# Flash_Fashion_Schematic_V2.net
KiCad netlist of a schematic drawn in EAGLE
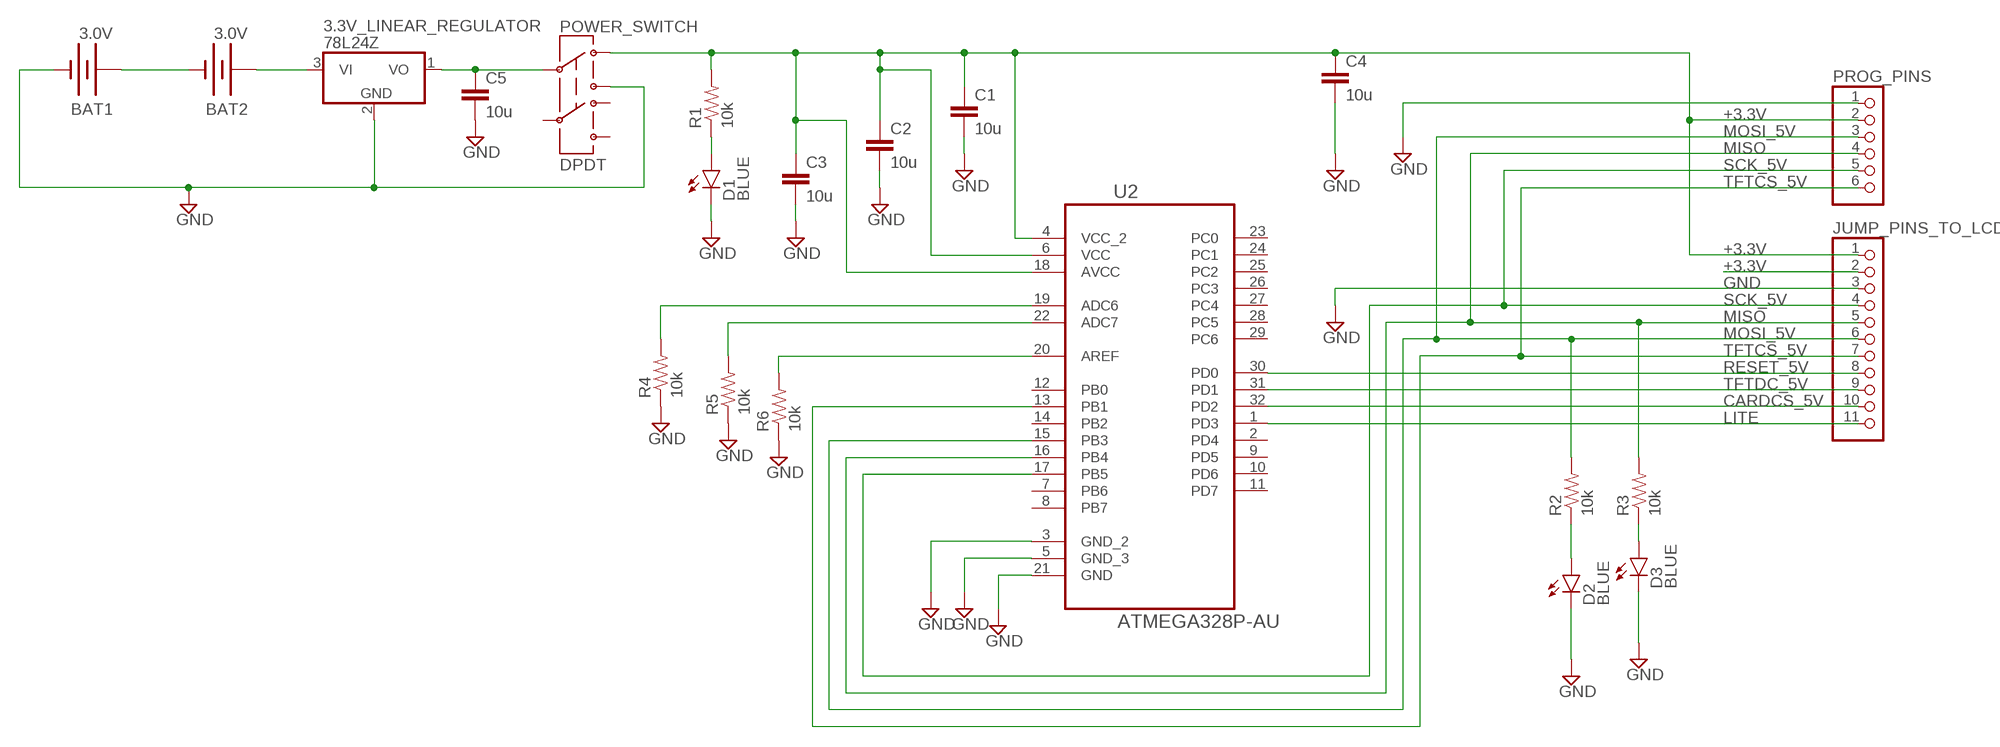
[diagram p0: schematic, sheet 1]

(export (version "E")
  (design (tool "Eeschema 10.0.6"))
  (components
    (comp (ref "3.3V_LINEAR_REGULATOR")
      (value "78L24Z")
      (footprint "eagle-import:TO92")
      (libsource (lib "eagle-import") (part "78ZL24"))
    )
    (comp (ref "BAT1")
      (value "3.0V")
      (footprint "eagle-import:BATTCON_245MM_PTH")
      (libsource (lib "eagle-import") (part "BATTERY245PTH"))
    )
    (comp (ref "BAT2")
      (value "3.0V")
      (footprint "eagle-import:BATTCON_245MM_PTH")
      (libsource (lib "eagle-import") (part "BATTERY245PTH"))
    )
    (comp (ref "C1")
      (value "10u")
      (footprint "eagle-import:1206")
      (libsource (lib "eagle-import") (part "CAP1206"))
    )
    (comp (ref "C2")
      (value "10u")
      (footprint "eagle-import:1206")
      (libsource (lib "eagle-import") (part "CAP1206"))
    )
    (comp (ref "C3")
      (value "10u")
      (footprint "eagle-import:1206")
      (libsource (lib "eagle-import") (part "CAP1206"))
    )
    (comp (ref "C4")
      (value "10u")
      (footprint "eagle-import:1206")
      (libsource (lib "eagle-import") (part "CAP1206"))
    )
    (comp (ref "C5")
      (value "10u")
      (footprint "eagle-import:1206")
      (libsource (lib "eagle-import") (part "CAP1206"))
    )
    (comp (ref "D1")
      (value "BLUE")
      (footprint "eagle-import:LED-1206")
      (libsource (lib "eagle-import") (part "LED-BLUE1206"))
    )
    (comp (ref "D2")
      (value "BLUE")
      (footprint "eagle-import:LED-1206")
      (libsource (lib "eagle-import") (part "LED-BLUE1206"))
    )
    (comp (ref "D3")
      (value "BLUE")
      (footprint "eagle-import:LED-1206")
      (libsource (lib "eagle-import") (part "LED-BLUE1206"))
    )
    (comp (ref "JUMP_PINS_TO_LCD")
      (value "HEADER-1X1176MIL")
      (footprint "eagle-import:1X11_ROUND_76")
      (libsource (lib "eagle-import") (part "HEADER-1X1176MIL"))
    )
    (comp (ref "POWER_SWITCH")
      (value "DPDT")
      (footprint "eagle-import:AYZ0202")
      (libsource (lib "eagle-import") (part "SWITCH-DPDTAYZ0202"))
    )
    (comp (ref "PROG_PINS")
      (value "PINHD-1X6-3.5MM")
      (footprint "eagle-import:1X06-3.5MM")
      (libsource (lib "eagle-import") (part "PINHD-1X6-3.5MM"))
    )
    (comp (ref "R1")
      (value "10k")
      (footprint "eagle-import:1206")
      (libsource (lib "eagle-import") (part "RESISTOR1206"))
    )
    (comp (ref "R2")
      (value "10k")
      (footprint "eagle-import:1206")
      (libsource (lib "eagle-import") (part "RESISTOR1206"))
    )
    (comp (ref "R3")
      (value "10k")
      (footprint "eagle-import:1206")
      (libsource (lib "eagle-import") (part "RESISTOR1206"))
    )
    (comp (ref "R4")
      (value "10k")
      (footprint "eagle-import:1206")
      (libsource (lib "eagle-import") (part "RESISTOR1206"))
    )
    (comp (ref "R5")
      (value "10k")
      (footprint "eagle-import:1206")
      (libsource (lib "eagle-import") (part "RESISTOR1206"))
    )
    (comp (ref "R6")
      (value "10k")
      (footprint "eagle-import:1206")
      (libsource (lib "eagle-import") (part "RESISTOR1206"))
    )
    (comp (ref "U2")
      (value "ATMEGA328P-AU")
      (footprint "eagle-import:QFP80P900X900X120-32N")
      (libsource (lib "eagle-import") (part "ATMEGA328P-AU"))
    )
  )
  (nets
    (net (code "1") (name "/+3.3V") (class "Default")
      (node (ref "C1") (pin "1") (pinfunction "1_1") (pintype "passive"))
      (node (ref "C2") (pin "1") (pinfunction "1_1") (pintype "passive"))
      (node (ref "C3") (pin "1") (pinfunction "1_1") (pintype "passive"))
      (node (ref "C4") (pin "1") (pinfunction "1_1") (pintype "passive"))
      (node (ref "JUMP_PINS_TO_LCD") (pin "1") (pinfunction "1_1") (pintype "passive"))
      (node (ref "POWER_SWITCH") (pin "1") (pinfunction "1_1") (pintype "bidirectional"))
      (node (ref "PROG_PINS") (pin "2") (pinfunction "2_2") (pintype "passive"))
      (node (ref "R1") (pin "2") (pinfunction "2_2") (pintype "passive"))
      (node (ref "U2") (pin "18") (pinfunction "AVCC_18") (pintype "power_in"))
      (node (ref "U2") (pin "4") (pinfunction "VCC_2_4") (pintype "power_in"))
      (node (ref "U2") (pin "6") (pinfunction "VCC_6") (pintype "power_in"))
    )
    (net (code "2") (name "/CARDCS_5V") (class "Default")
      (node (ref "JUMP_PINS_TO_LCD") (pin "10") (pinfunction "10_10") (pintype "passive"))
      (node (ref "U2") (pin "32") (pinfunction "PD2_32") (pintype "bidirectional"))
    )
    (net (code "3") (name "/LITE") (class "Default")
      (node (ref "JUMP_PINS_TO_LCD") (pin "11") (pinfunction "11_11") (pintype "passive"))
      (node (ref "U2") (pin "1") (pinfunction "PD3_1") (pintype "bidirectional"))
    )
    (net (code "4") (name "/MISO") (class "Default")
      (node (ref "JUMP_PINS_TO_LCD") (pin "5") (pinfunction "5_5") (pintype "passive"))
      (node (ref "PROG_PINS") (pin "4") (pinfunction "4_4") (pintype "passive"))
      (node (ref "R3") (pin "2") (pinfunction "2_2") (pintype "passive"))
      (node (ref "U2") (pin "16") (pinfunction "PB4_16") (pintype "bidirectional"))
    )
    (net (code "5") (name "/MOSI_5V") (class "Default")
      (node (ref "JUMP_PINS_TO_LCD") (pin "6") (pinfunction "6_6") (pintype "passive"))
      (node (ref "PROG_PINS") (pin "3") (pinfunction "3_3") (pintype "passive"))
      (node (ref "R2") (pin "2") (pinfunction "2_2") (pintype "passive"))
      (node (ref "U2") (pin "15") (pinfunction "PB3_15") (pintype "bidirectional"))
    )
    (net (code "6") (name "/RESET_5V") (class "Default")
      (node (ref "JUMP_PINS_TO_LCD") (pin "8") (pinfunction "8_8") (pintype "passive"))
      (node (ref "U2") (pin "30") (pinfunction "PD0_30") (pintype "bidirectional"))
    )
    (net (code "7") (name "/SCK_5V") (class "Default")
      (node (ref "JUMP_PINS_TO_LCD") (pin "4") (pinfunction "4_4") (pintype "passive"))
      (node (ref "PROG_PINS") (pin "5") (pinfunction "5_5") (pintype "passive"))
      (node (ref "U2") (pin "17") (pinfunction "PB5_17") (pintype "bidirectional"))
    )
    (net (code "8") (name "/TFTCS_5V") (class "Default")
      (node (ref "JUMP_PINS_TO_LCD") (pin "7") (pinfunction "7_7") (pintype "passive"))
      (node (ref "PROG_PINS") (pin "6") (pinfunction "6_6") (pintype "passive"))
      (node (ref "U2") (pin "13") (pinfunction "PB1_13") (pintype "bidirectional"))
    )
    (net (code "9") (name "/TFTDC_5V") (class "Default")
      (node (ref "JUMP_PINS_TO_LCD") (pin "9") (pinfunction "9_9") (pintype "passive"))
      (node (ref "U2") (pin "31") (pinfunction "PD1_31") (pintype "bidirectional"))
    )
    (net (code "10") (name "GND") (class "Default")
      (node (ref "3.3V_LINEAR_REGULATOR") (pin "2") (pinfunction "GND_2") (pintype "passive"))
      (node (ref "BAT1") (pin "2") (pinfunction "-_2") (pintype "power_in"))
      (node (ref "C1") (pin "2") (pinfunction "2_2") (pintype "passive"))
      (node (ref "C2") (pin "2") (pinfunction "2_2") (pintype "passive"))
      (node (ref "C3") (pin "2") (pinfunction "2_2") (pintype "passive"))
      (node (ref "C4") (pin "2") (pinfunction "2_2") (pintype "passive"))
      (node (ref "C5") (pin "2") (pinfunction "2_2") (pintype "passive"))
      (node (ref "D1") (pin "C") (pinfunction "C_C") (pintype "passive"))
      (node (ref "D2") (pin "C") (pinfunction "C_C") (pintype "passive"))
      (node (ref "D3") (pin "C") (pinfunction "C_C") (pintype "passive"))
      (node (ref "JUMP_PINS_TO_LCD") (pin "3") (pinfunction "3_3") (pintype "passive"))
      (node (ref "POWER_SWITCH") (pin "3") (pinfunction "3_3") (pintype "bidirectional"))
      (node (ref "PROG_PINS") (pin "1") (pinfunction "1_1") (pintype "passive"))
      (node (ref "R4") (pin "1") (pinfunction "1_1") (pintype "passive"))
      (node (ref "R5") (pin "1") (pinfunction "1_1") (pintype "passive"))
      (node (ref "R6") (pin "1") (pinfunction "1_1") (pintype "passive"))
      (node (ref "U2") (pin "21") (pinfunction "GND_21") (pintype "passive"))
      (node (ref "U2") (pin "3") (pinfunction "GND_2_3") (pintype "passive"))
      (node (ref "U2") (pin "5") (pinfunction "GND_3_5") (pintype "passive"))
    )
    (net (code "11") (name "Net-(3.3V_LINEAR_REGULATOR-VI)") (class "Default")
      (node (ref "3.3V_LINEAR_REGULATOR") (pin "3") (pinfunction "VI_3") (pintype "input"))
      (node (ref "BAT2") (pin "3") (pinfunction "+_3") (pintype "power_in"))
    )
    (net (code "12") (name "Net-(3.3V_LINEAR_REGULATOR-VO)") (class "Default")
      (node (ref "3.3V_LINEAR_REGULATOR") (pin "1") (pinfunction "VO_1") (pintype "passive"))
      (node (ref "C5") (pin "1") (pinfunction "1_1") (pintype "passive"))
      (node (ref "POWER_SWITCH") (pin "2") (pinfunction "2_2") (pintype "bidirectional"))
    )
    (net (code "13") (name "Net-(BAT1-+)") (class "Default")
      (node (ref "BAT1") (pin "3") (pinfunction "+_3") (pintype "power_in"))
      (node (ref "BAT2") (pin "2") (pinfunction "-_2") (pintype "power_in"))
    )
    (net (code "14") (name "Net-(D1-PadA)") (class "Default")
      (node (ref "D1") (pin "A") (pinfunction "A_A") (pintype "passive"))
      (node (ref "R1") (pin "1") (pinfunction "1_1") (pintype "passive"))
    )
    (net (code "15") (name "Net-(D2-PadA)") (class "Default")
      (node (ref "D2") (pin "A") (pinfunction "A_A") (pintype "passive"))
      (node (ref "R2") (pin "1") (pinfunction "1_1") (pintype "passive"))
    )
    (net (code "16") (name "Net-(D3-PadA)") (class "Default")
      (node (ref "D3") (pin "A") (pinfunction "A_A") (pintype "passive"))
      (node (ref "R3") (pin "1") (pinfunction "1_1") (pintype "passive"))
    )
    (net (code "17") (name "Net-(U2-ADC6)") (class "Default")
      (node (ref "R4") (pin "2") (pinfunction "2_2") (pintype "passive"))
      (node (ref "U2") (pin "19") (pinfunction "ADC6_19") (pintype "input"))
    )
    (net (code "18") (name "Net-(U2-ADC7)") (class "Default")
      (node (ref "R5") (pin "2") (pinfunction "2_2") (pintype "passive"))
      (node (ref "U2") (pin "22") (pinfunction "ADC7_22") (pintype "input"))
    )
    (net (code "19") (name "Net-(U2-AREF)") (class "Default")
      (node (ref "R6") (pin "2") (pinfunction "2_2") (pintype "passive"))
      (node (ref "U2") (pin "20") (pinfunction "AREF_20") (pintype "input"))
    )
    (net (code "20") (name "unconnected-(JUMP_PINS_TO_LCD-Pad2)") (class "Default")
      (node (ref "JUMP_PINS_TO_LCD") (pin "2") (pinfunction "2_2") (pintype "passive"))
    )
    (net (code "21") (name "unconnected-(POWER_SWITCH-Pad4)") (class "Default")
      (node (ref "POWER_SWITCH") (pin "4") (pinfunction "4_4") (pintype "bidirectional"))
    )
    (net (code "22") (name "unconnected-(POWER_SWITCH-Pad5)") (class "Default")
      (node (ref "POWER_SWITCH") (pin "5") (pinfunction "5_5") (pintype "bidirectional"))
    )
    (net (code "23") (name "unconnected-(POWER_SWITCH-Pad6)") (class "Default")
      (node (ref "POWER_SWITCH") (pin "6") (pinfunction "6_6") (pintype "bidirectional"))
    )
    (net (code "24") (name "unconnected-(U2-PB0-Pad12)") (class "Default")
      (node (ref "U2") (pin "12") (pinfunction "PB0_12") (pintype "bidirectional"))
    )
    (net (code "25") (name "unconnected-(U2-PB2-Pad14)") (class "Default")
      (node (ref "U2") (pin "14") (pinfunction "PB2_14") (pintype "bidirectional"))
    )
    (net (code "26") (name "unconnected-(U2-PB6-Pad7)") (class "Default")
      (node (ref "U2") (pin "7") (pinfunction "PB6_7") (pintype "bidirectional"))
    )
    (net (code "27") (name "unconnected-(U2-PB7-Pad8)") (class "Default")
      (node (ref "U2") (pin "8") (pinfunction "PB7_8") (pintype "bidirectional"))
    )
    (net (code "28") (name "unconnected-(U2-PC0-Pad23)") (class "Default")
      (node (ref "U2") (pin "23") (pinfunction "PC0_23") (pintype "bidirectional"))
    )
    (net (code "29") (name "unconnected-(U2-PC1-Pad24)") (class "Default")
      (node (ref "U2") (pin "24") (pinfunction "PC1_24") (pintype "bidirectional"))
    )
    (net (code "30") (name "unconnected-(U2-PC2-Pad25)") (class "Default")
      (node (ref "U2") (pin "25") (pinfunction "PC2_25") (pintype "bidirectional"))
    )
    (net (code "31") (name "unconnected-(U2-PC3-Pad26)") (class "Default")
      (node (ref "U2") (pin "26") (pinfunction "PC3_26") (pintype "bidirectional"))
    )
    (net (code "32") (name "unconnected-(U2-PC4-Pad27)") (class "Default")
      (node (ref "U2") (pin "27") (pinfunction "PC4_27") (pintype "bidirectional"))
    )
    (net (code "33") (name "unconnected-(U2-PC5-Pad28)") (class "Default")
      (node (ref "U2") (pin "28") (pinfunction "PC5_28") (pintype "bidirectional"))
    )
    (net (code "34") (name "unconnected-(U2-PC6-Pad29)") (class "Default")
      (node (ref "U2") (pin "29") (pinfunction "PC6_29") (pintype "bidirectional"))
    )
    (net (code "35") (name "unconnected-(U2-PD4-Pad2)") (class "Default")
      (node (ref "U2") (pin "2") (pinfunction "PD4_2") (pintype "bidirectional"))
    )
    (net (code "36") (name "unconnected-(U2-PD5-Pad9)") (class "Default")
      (node (ref "U2") (pin "9") (pinfunction "PD5_9") (pintype "bidirectional"))
    )
    (net (code "37") (name "unconnected-(U2-PD6-Pad10)") (class "Default")
      (node (ref "U2") (pin "10") (pinfunction "PD6_10") (pintype "bidirectional"))
    )
    (net (code "38") (name "unconnected-(U2-PD7-Pad11)") (class "Default")
      (node (ref "U2") (pin "11") (pinfunction "PD7_11") (pintype "bidirectional"))
    )
  )
)
